# CSI_connectors.net
KiCad netlist of a schematic drawn in Altium Designer
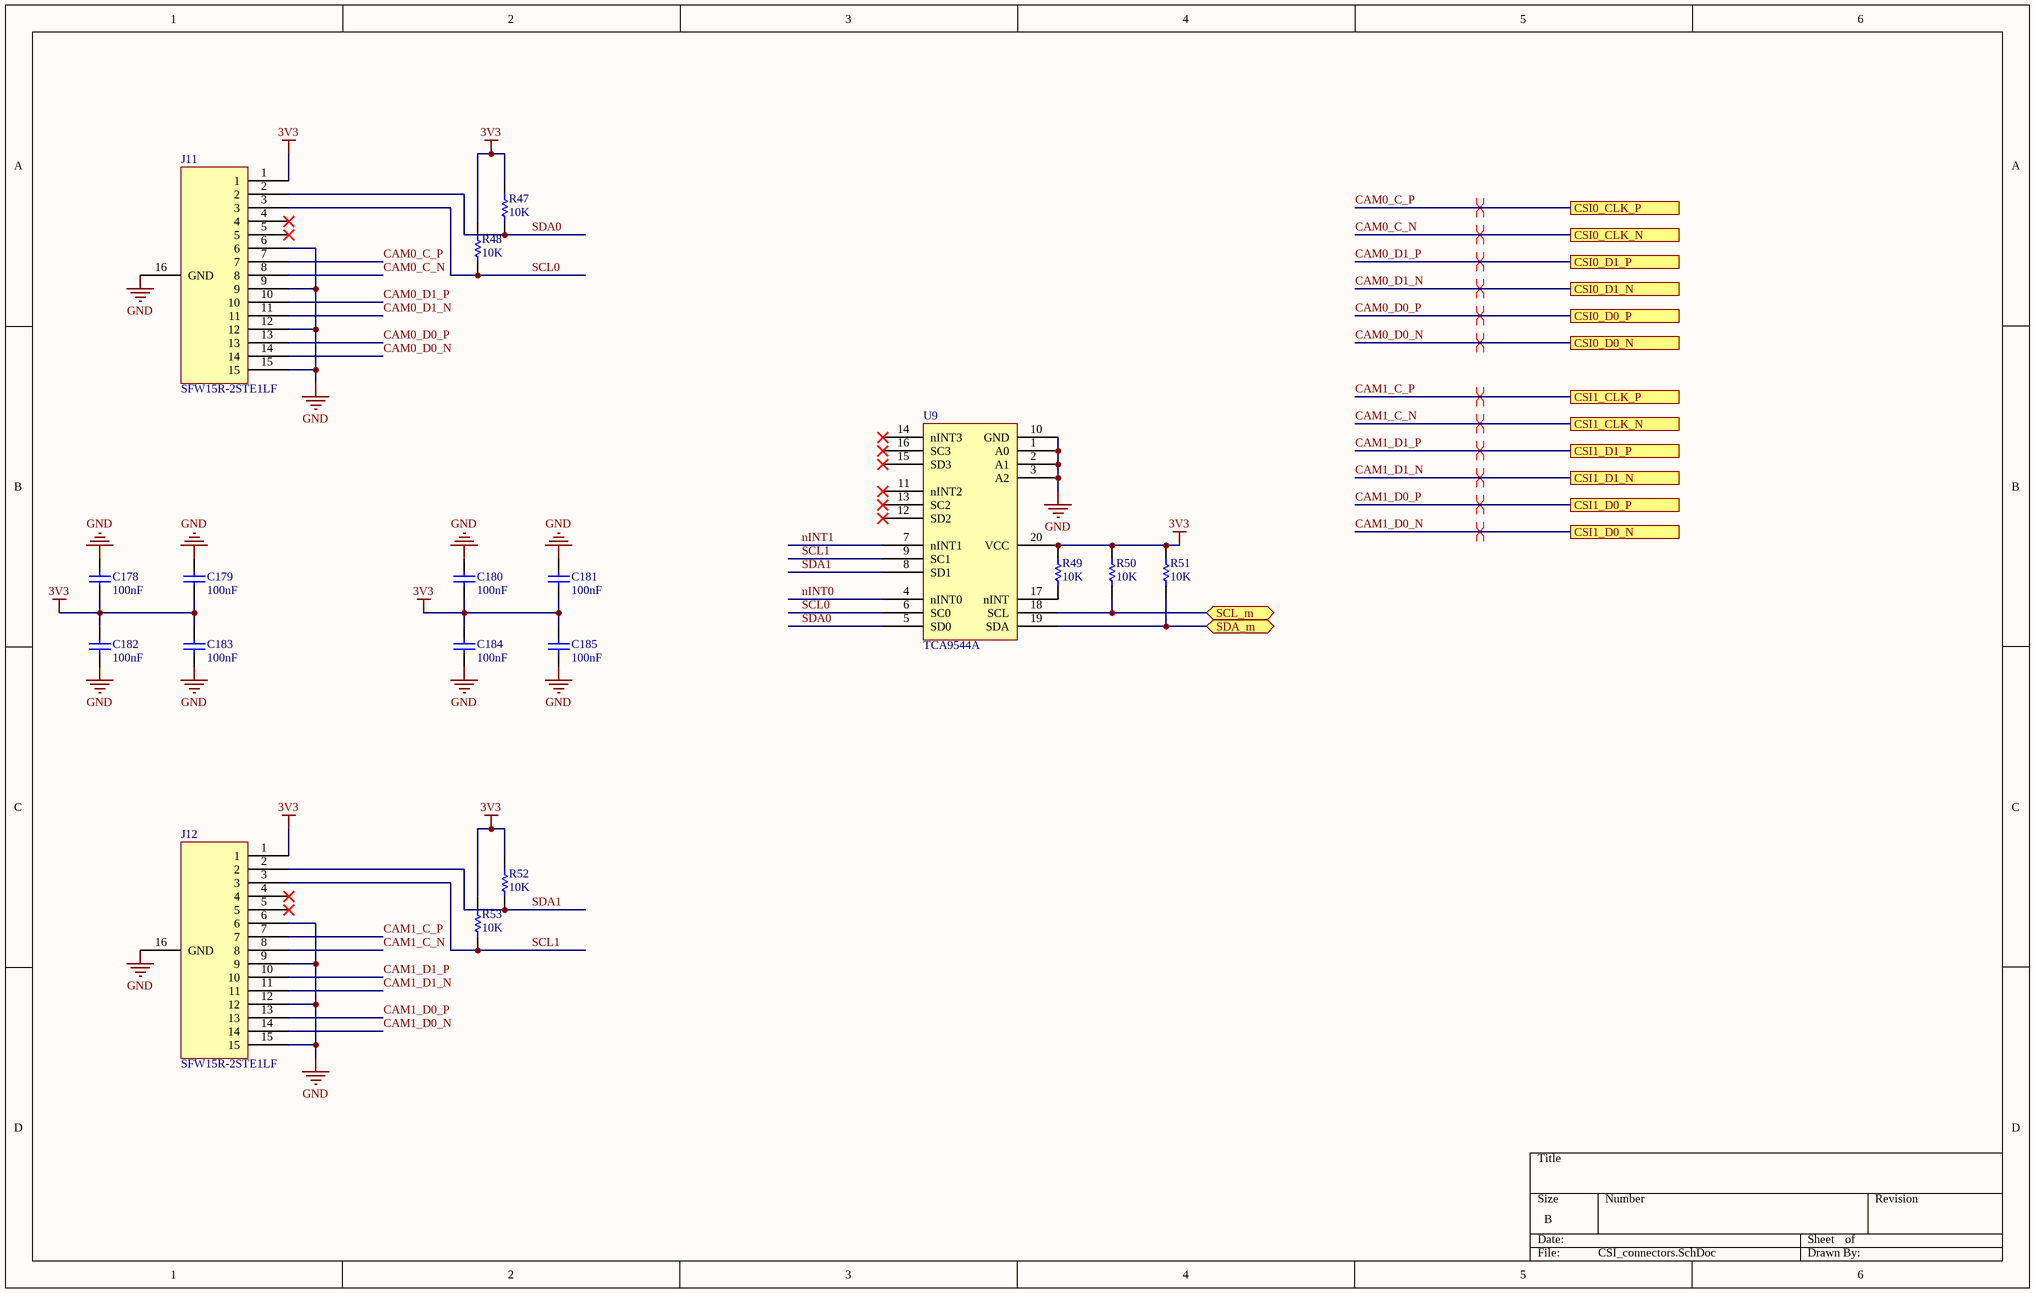
[diagram p0: CSI_connectors.SchDoc]

(export (version "E")
  (design (tool "Eeschema 10.0.6"))
  (components
    (comp (ref "C178")
      (value "100nF")
      (footprint "CAPC0603(1608)100_N")
      (description "100nF 10V")
      (fields (field (name "TOLERANCE") "Â±10%"))
      (libsource (lib "my_schsymbols") (part "CAP_0603"))
    )
    (comp (ref "C179")
      (value "100nF")
      (footprint "CAPC0603(1608)100_N")
      (description "100nF 10V")
      (fields (field (name "TOLERANCE") "Â±10%"))
      (libsource (lib "my_schsymbols") (part "CAP_0603"))
    )
    (comp (ref "C180")
      (value "100nF")
      (footprint "CAPC0603(1608)100_N")
      (description "100nF 10V")
      (fields (field (name "TOLERANCE") "Â±10%"))
      (libsource (lib "my_schsymbols") (part "CAP_0603"))
    )
    (comp (ref "C181")
      (value "100nF")
      (footprint "CAPC0603(1608)100_N")
      (description "100nF 10V")
      (fields (field (name "TOLERANCE") "Â±10%"))
      (libsource (lib "my_schsymbols") (part "CAP_0603"))
    )
    (comp (ref "C182")
      (value "100nF")
      (footprint "CAPC0603(1608)100_N")
      (description "100nF 10V")
      (fields (field (name "TOLERANCE") "Â±10%"))
      (libsource (lib "my_schsymbols") (part "CAP_0603"))
    )
    (comp (ref "C183")
      (value "100nF")
      (footprint "CAPC0603(1608)100_N")
      (description "100nF 10V")
      (fields (field (name "TOLERANCE") "Â±10%"))
      (libsource (lib "my_schsymbols") (part "CAP_0603"))
    )
    (comp (ref "C184")
      (value "100nF")
      (footprint "CAPC0603(1608)100_N")
      (description "100nF 10V")
      (fields (field (name "TOLERANCE") "Â±10%"))
      (libsource (lib "my_schsymbols") (part "CAP_0603"))
    )
    (comp (ref "C185")
      (value "100nF")
      (footprint "CAPC0603(1608)100_N")
      (description "100nF 10V")
      (fields (field (name "TOLERANCE") "Â±10%"))
      (libsource (lib "my_schsymbols") (part "CAP_0603"))
    )
    (comp (ref "J11")
      (value "SFW15R-2STE1LF")
      (footprint "SFW15R-2STE1LF")
      (libsource (lib "my_schsymbols") (part "SFW15R-2STE1LF"))
    )
    (comp (ref "J12")
      (value "SFW15R-2STE1LF")
      (footprint "SFW15R-2STE1LF")
      (libsource (lib "my_schsymbols") (part "SFW15R-2STE1LF"))
    )
    (comp (ref "R47")
      (value "10K")
      (footprint "RESC0603(1608)_N")
      (description "10K 0.1W 1% 0603 (1608 Metric)  SMD")
      (fields (field (name "POWER") "0.1 W") (field (name "TOLERANCE") "1 %"))
      (libsource (lib "Altium Content Vault") (part "RES"))
    )
    (comp (ref "R48")
      (value "10K")
      (footprint "RESC0603(1608)_N")
      (description "10K 0.1W 1% 0603 (1608 Metric)  SMD")
      (fields (field (name "POWER") "0.1 W") (field (name "TOLERANCE") "1 %"))
      (libsource (lib "Altium Content Vault") (part "RES"))
    )
    (comp (ref "R49")
      (value "10K")
      (footprint "RESC0603(1608)_N")
      (description "10K 0.1W 1% 0603 (1608 Metric)  SMD")
      (fields (field (name "POWER") "0.1 W") (field (name "TOLERANCE") "1 %"))
      (libsource (lib "Altium Content Vault") (part "RES"))
    )
    (comp (ref "R50")
      (value "10K")
      (footprint "RESC0603(1608)_N")
      (description "10K 0.1W 1% 0603 (1608 Metric)  SMD")
      (fields (field (name "POWER") "0.1 W") (field (name "TOLERANCE") "1 %"))
      (libsource (lib "Altium Content Vault") (part "RES"))
    )
    (comp (ref "R51")
      (value "10K")
      (footprint "RESC0603(1608)_N")
      (description "10K 0.1W 1% 0603 (1608 Metric)  SMD")
      (fields (field (name "POWER") "0.1 W") (field (name "TOLERANCE") "1 %"))
      (libsource (lib "Altium Content Vault") (part "RES"))
    )
    (comp (ref "R52")
      (value "10K")
      (footprint "RESC0603(1608)_N")
      (description "10K 0.1W 1% 0603 (1608 Metric)  SMD")
      (fields (field (name "POWER") "0.1 W") (field (name "TOLERANCE") "1 %"))
      (libsource (lib "Altium Content Vault") (part "RES"))
    )
    (comp (ref "R53")
      (value "10K")
      (footprint "RESC0603(1608)_N")
      (description "10K 0.1W 1% 0603 (1608 Metric)  SMD")
      (fields (field (name "POWER") "0.1 W") (field (name "TOLERANCE") "1 %"))
      (libsource (lib "Altium Content Vault") (part "RES"))
    )
    (comp (ref "U9")
      (value "TCA9544A")
      (footprint "TSOP65P640X120-20N")
      (description "Low Voltage 4-Channel I\r\n2C and SMBus Multiplexer With Interrupt Logic")
      (libsource (lib "CGRA_schlib") (part "TCA9544A"))
    )
  )
  (nets
    (net (code "1") (name "/CAM0_C_N") (class "Default")
      (node (ref "J11") (pin "8") (pinfunction "8_8") (pintype "passive"))
    )
    (net (code "2") (name "/CAM0_C_P") (class "Default")
      (node (ref "J11") (pin "7") (pinfunction "7_7") (pintype "passive"))
    )
    (net (code "3") (name "/CAM0_D0_N") (class "Default")
      (node (ref "J11") (pin "14") (pinfunction "14_14") (pintype "passive"))
    )
    (net (code "4") (name "/CAM0_D0_P") (class "Default")
      (node (ref "J11") (pin "13") (pinfunction "13_13") (pintype "passive"))
    )
    (net (code "5") (name "/CAM0_D1_N") (class "Default")
      (node (ref "J11") (pin "11") (pinfunction "11_11") (pintype "passive"))
    )
    (net (code "6") (name "/CAM0_D1_P") (class "Default")
      (node (ref "J11") (pin "10") (pinfunction "10_10") (pintype "passive"))
    )
    (net (code "7") (name "/CAM1_C_N") (class "Default")
      (node (ref "J12") (pin "8") (pinfunction "8_8") (pintype "passive"))
    )
    (net (code "8") (name "/CAM1_C_P") (class "Default")
      (node (ref "J12") (pin "7") (pinfunction "7_7") (pintype "passive"))
    )
    (net (code "9") (name "/CAM1_D0_N") (class "Default")
      (node (ref "J12") (pin "14") (pinfunction "14_14") (pintype "passive"))
    )
    (net (code "10") (name "/CAM1_D0_P") (class "Default")
      (node (ref "J12") (pin "13") (pinfunction "13_13") (pintype "passive"))
    )
    (net (code "11") (name "/CAM1_D1_N") (class "Default")
      (node (ref "J12") (pin "11") (pinfunction "11_11") (pintype "passive"))
    )
    (net (code "12") (name "/CAM1_D1_P") (class "Default")
      (node (ref "J12") (pin "10") (pinfunction "10_10") (pintype "passive"))
    )
    (net (code "13") (name "/SCL0") (class "Default")
      (node (ref "J11") (pin "3") (pinfunction "3_3") (pintype "passive"))
      (node (ref "R48") (pin "1") (pinfunction "1_1") (pintype "passive"))
      (node (ref "U9") (pin "6") (pinfunction "SC0_6") (pintype "passive"))
    )
    (net (code "14") (name "/SCL1") (class "Default")
      (node (ref "J12") (pin "3") (pinfunction "3_3") (pintype "passive"))
      (node (ref "R53") (pin "1") (pinfunction "1_1") (pintype "passive"))
      (node (ref "U9") (pin "9") (pinfunction "SC1_9") (pintype "passive"))
    )
    (net (code "15") (name "/SCL_m") (class "Default")
      (node (ref "R50") (pin "1") (pinfunction "1_1") (pintype "passive"))
      (node (ref "U9") (pin "18") (pinfunction "SCL_18") (pintype "passive"))
    )
    (net (code "16") (name "/SDA0") (class "Default")
      (node (ref "J11") (pin "2") (pinfunction "2_2") (pintype "passive"))
      (node (ref "R47") (pin "1") (pinfunction "1_1") (pintype "passive"))
      (node (ref "U9") (pin "5") (pinfunction "SD0_5") (pintype "passive"))
    )
    (net (code "17") (name "/SDA1") (class "Default")
      (node (ref "J12") (pin "2") (pinfunction "2_2") (pintype "passive"))
      (node (ref "R52") (pin "1") (pinfunction "1_1") (pintype "passive"))
      (node (ref "U9") (pin "8") (pinfunction "SD1_8") (pintype "passive"))
    )
    (net (code "18") (name "/SDA_m") (class "Default")
      (node (ref "R51") (pin "1") (pinfunction "1_1") (pintype "passive"))
      (node (ref "U9") (pin "19") (pinfunction "SDA_19") (pintype "passive"))
    )
    (net (code "19") (name "/nINT0") (class "Default")
      (node (ref "U9") (pin "4") (pinfunction "nINT0_4") (pintype "passive"))
    )
    (net (code "20") (name "/nINT1") (class "Default")
      (node (ref "U9") (pin "7") (pinfunction "nINT1_7") (pintype "passive"))
    )
    (net (code "21") (name "3V3") (class "Default")
      (node (ref "C178") (pin "1") (pinfunction "1_1") (pintype "passive"))
      (node (ref "C179") (pin "1") (pinfunction "1_1") (pintype "passive"))
      (node (ref "C180") (pin "1") (pinfunction "1_1") (pintype "passive"))
      (node (ref "C181") (pin "1") (pinfunction "1_1") (pintype "passive"))
      (node (ref "C182") (pin "2") (pinfunction "2_2") (pintype "passive"))
      (node (ref "C183") (pin "2") (pinfunction "2_2") (pintype "passive"))
      (node (ref "C184") (pin "2") (pinfunction "2_2") (pintype "passive"))
      (node (ref "C185") (pin "2") (pinfunction "2_2") (pintype "passive"))
      (node (ref "J11") (pin "1") (pinfunction "1_1") (pintype "passive"))
      (node (ref "J12") (pin "1") (pinfunction "1_1") (pintype "passive"))
      (node (ref "R47") (pin "2") (pinfunction "2_2") (pintype "passive"))
      (node (ref "R48") (pin "2") (pinfunction "2_2") (pintype "passive"))
      (node (ref "R49") (pin "2") (pinfunction "2_2") (pintype "passive"))
      (node (ref "R50") (pin "2") (pinfunction "2_2") (pintype "passive"))
      (node (ref "R51") (pin "2") (pinfunction "2_2") (pintype "passive"))
      (node (ref "R52") (pin "2") (pinfunction "2_2") (pintype "passive"))
      (node (ref "R53") (pin "2") (pinfunction "2_2") (pintype "passive"))
      (node (ref "U9") (pin "20") (pinfunction "VCC_20") (pintype "passive"))
    )
    (net (code "22") (name "GND") (class "Default")
      (node (ref "C178") (pin "2") (pinfunction "2_2") (pintype "passive"))
      (node (ref "C179") (pin "2") (pinfunction "2_2") (pintype "passive"))
      (node (ref "C180") (pin "2") (pinfunction "2_2") (pintype "passive"))
      (node (ref "C181") (pin "2") (pinfunction "2_2") (pintype "passive"))
      (node (ref "C182") (pin "1") (pinfunction "1_1") (pintype "passive"))
      (node (ref "C183") (pin "1") (pinfunction "1_1") (pintype "passive"))
      (node (ref "C184") (pin "1") (pinfunction "1_1") (pintype "passive"))
      (node (ref "C185") (pin "1") (pinfunction "1_1") (pintype "passive"))
      (node (ref "J11") (pin "12") (pinfunction "12_12") (pintype "passive"))
      (node (ref "J11") (pin "15") (pinfunction "15_15") (pintype "passive"))
      (node (ref "J11") (pin "16") (pinfunction "GND_16") (pintype "passive"))
      (node (ref "J11") (pin "6") (pinfunction "6_6") (pintype "passive"))
      (node (ref "J11") (pin "9") (pinfunction "9_9") (pintype "passive"))
      (node (ref "J12") (pin "12") (pinfunction "12_12") (pintype "passive"))
      (node (ref "J12") (pin "15") (pinfunction "15_15") (pintype "passive"))
      (node (ref "J12") (pin "16") (pinfunction "GND_16") (pintype "passive"))
      (node (ref "J12") (pin "6") (pinfunction "6_6") (pintype "passive"))
      (node (ref "J12") (pin "9") (pinfunction "9_9") (pintype "passive"))
      (node (ref "U9") (pin "1") (pinfunction "A0_1") (pintype "passive"))
      (node (ref "U9") (pin "10") (pinfunction "GND_10") (pintype "passive"))
      (node (ref "U9") (pin "2") (pinfunction "A1_2") (pintype "passive"))
      (node (ref "U9") (pin "3") (pinfunction "A2_3") (pintype "passive"))
    )
    (net (code "23") (name "Net-(U9-nINT)") (class "Default")
      (node (ref "R49") (pin "1") (pinfunction "1_1") (pintype "passive"))
      (node (ref "U9") (pin "17") (pinfunction "nINT_17") (pintype "passive"))
    )
    (net (code "24") (name "unconnected-(J11-Pad4)") (class "Default")
      (node (ref "J11") (pin "4") (pinfunction "4_4") (pintype "passive+no_connect"))
    )
    (net (code "25") (name "unconnected-(J11-Pad5)") (class "Default")
      (node (ref "J11") (pin "5") (pinfunction "5_5") (pintype "passive+no_connect"))
    )
    (net (code "26") (name "unconnected-(J12-Pad4)") (class "Default")
      (node (ref "J12") (pin "4") (pinfunction "4_4") (pintype "passive+no_connect"))
    )
    (net (code "27") (name "unconnected-(J12-Pad5)") (class "Default")
      (node (ref "J12") (pin "5") (pinfunction "5_5") (pintype "passive+no_connect"))
    )
    (net (code "28") (name "unconnected-(U9-SC2-Pad13)") (class "Default")
      (node (ref "U9") (pin "13") (pinfunction "SC2_13") (pintype "passive+no_connect"))
    )
    (net (code "29") (name "unconnected-(U9-SC3-Pad16)") (class "Default")
      (node (ref "U9") (pin "16") (pinfunction "SC3_16") (pintype "passive+no_connect"))
    )
    (net (code "30") (name "unconnected-(U9-SD2-Pad12)") (class "Default")
      (node (ref "U9") (pin "12") (pinfunction "SD2_12") (pintype "passive+no_connect"))
    )
    (net (code "31") (name "unconnected-(U9-SD3-Pad15)") (class "Default")
      (node (ref "U9") (pin "15") (pinfunction "SD3_15") (pintype "passive+no_connect"))
    )
    (net (code "32") (name "unconnected-(U9-nINT2-Pad11)") (class "Default")
      (node (ref "U9") (pin "11") (pinfunction "nINT2_11") (pintype "passive+no_connect"))
    )
    (net (code "33") (name "unconnected-(U9-nINT3-Pad14)") (class "Default")
      (node (ref "U9") (pin "14") (pinfunction "nINT3_14") (pintype "passive+no_connect"))
    )
  )
)
